# NO2-CO_Schematic.net
KiCad netlist of a schematic drawn in Altium Designer
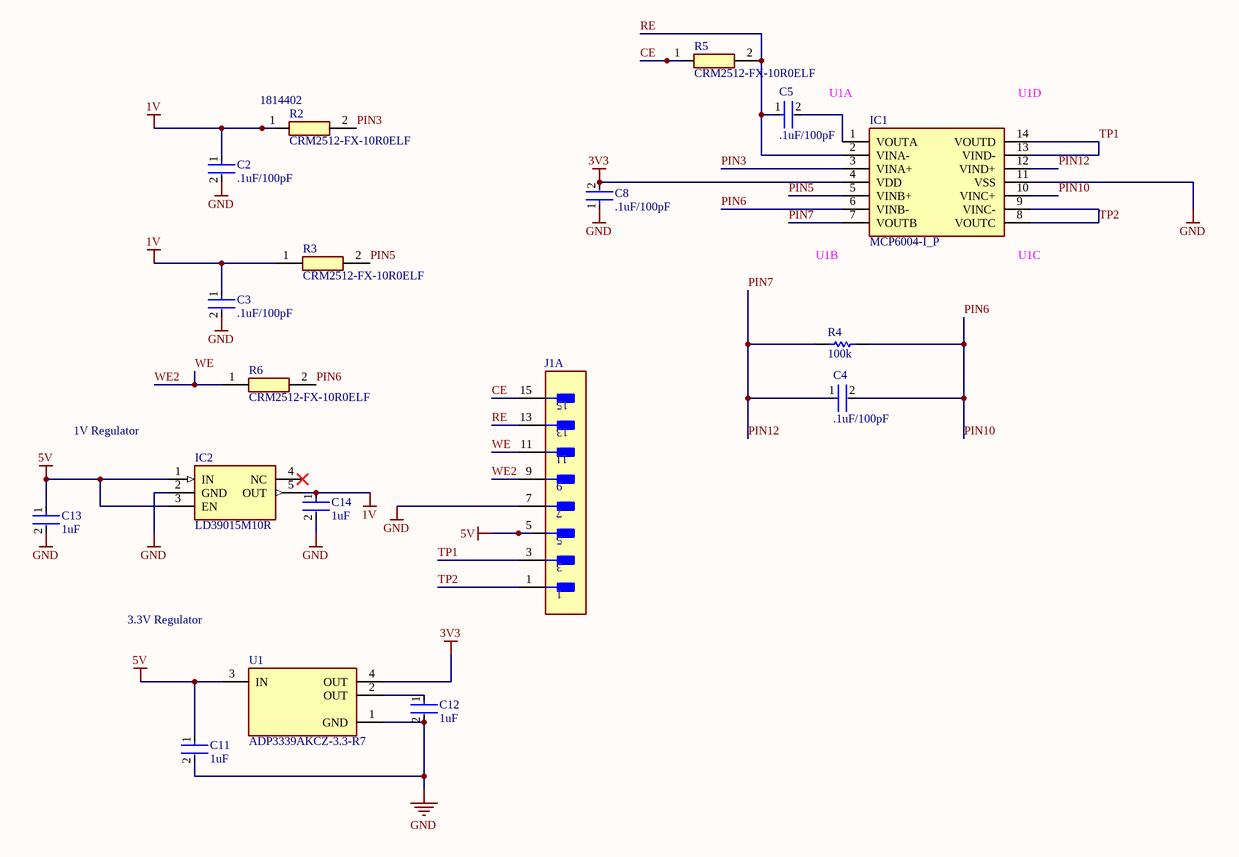
[diagram p0: NO2-CO Schematic.SchDoc]

(export (version "E")
  (design (tool "Eeschema 10.0.6"))
  (components
    (comp (ref "C2")
      (value ".1uF/100pF")
      (footprint "FP-RCE0DB-MFG")
      (description "Cap Ceramic 100pF 100V C0G ±5% Radial 2.5mm +125°C Ammo Pack")
      (fields (field (name "TOLERANCE") "5%"))
      (libsource (lib "Altium Content Vault") (part "b4654b650e69147ec39a6b967a45e02"))
    )
    (comp (ref "C3")
      (value ".1uF/100pF")
      (footprint "FP-RCE0DB-MFG")
      (description "Cap Ceramic 100pF 100V C0G ±5% Radial 2.5mm +125°C Ammo Pack")
      (fields (field (name "TOLERANCE") "5%"))
      (libsource (lib "Altium Content Vault") (part "b4654b650e69147ec39a6b967a45e02"))
    )
    (comp (ref "C4")
      (value ".1uF/100pF")
      (footprint "FP-RCE0DB-MFG")
      (description "Cap Ceramic 100pF 100V C0G ±5% Radial 2.5mm +125°C Ammo Pack")
      (fields (field (name "TOLERANCE") "5%"))
      (libsource (lib "Altium Content Vault") (part "b4654b650e69147ec39a6b967a45e02"))
    )
    (comp (ref "C5")
      (value ".1uF/100pF")
      (footprint "FP-RCE0DB-MFG")
      (description "Cap Ceramic 100pF 100V C0G ±5% Radial 2.5mm +125°C Ammo Pack")
      (fields (field (name "TOLERANCE") "5%"))
      (libsource (lib "Altium Content Vault") (part "b4654b650e69147ec39a6b967a45e02"))
    )
    (comp (ref "C8")
      (value ".1uF/100pF")
      (footprint "FP-RCE0DB-MFG")
      (description "Cap Ceramic 100pF 100V C0G ±5% Radial 2.5mm +125°C Ammo Pack")
      (fields (field (name "TOLERANCE") "5%"))
      (libsource (lib "Altium Content Vault") (part "b4654b650e69147ec39a6b967a45e02"))
    )
    (comp (ref "C11")
      (value "1uF")
      (footprint "FP-0603-L_1_6_0_1-W_0_8_0-IPC_B")
      (description "None")
      (fields (field (name "TOLERANCE") "10%"))
      (libsource (lib "Altium Content Vault") (part "02cd4be3c70576c341d710602a673aa"))
    )
    (comp (ref "C12")
      (value "1uF")
      (footprint "FP-0603-L_1_6_0_1-W_0_8_0-IPC_B")
      (description "None")
      (fields (field (name "TOLERANCE") "10%"))
      (libsource (lib "Altium Content Vault") (part "02cd4be3c70576c341d710602a673aa"))
    )
    (comp (ref "C13")
      (value "1uF")
      (footprint "FP-0603-L_1_6_0_1-W_0_8_0-IPC_B")
      (description "None")
      (fields (field (name "TOLERANCE") "10%"))
      (libsource (lib "Altium Content Vault") (part "02cd4be3c70576c341d710602a673aa"))
    )
    (comp (ref "C14")
      (value "1uF")
      (footprint "FP-0603-L_1_6_0_1-W_0_8_0-IPC_B")
      (description "None")
      (fields (field (name "TOLERANCE") "10%"))
      (libsource (lib "Altium Content Vault") (part "02cd4be3c70576c341d710602a673aa"))
    )
    (comp (ref "IC1")
      (value "MCP6004-I_P")
      (footprint "SamacSys:DIP794W56P254L1905H432Q14N")
      (description "Integrated Circuit")
      (fields
        (field (name "MANUFACTURER_PART_NUMBER") "MCP6004-I/P")
        (field (name "MOUSER PART NUMBER") "579-MCP6004-I/P")
      )
      (libsource (lib "*") (part "MCP6004-I_P"))
    )
    (comp (ref "IC2")
      (value "LD39015M10R")
      (footprint "SamacSys:SOT95P280X145-5N")
      (description "Integrated Circuit")
      (fields (field (name "MOUSER PART NUMBER") "511-LD39015M10R"))
      (libsource (lib "*") (part "LD39015M10R"))
    )
    (comp (ref "J1")
      (value "~")
      (footprint "FP-87227-8-MFG")
      (description "CONN HEADER VERT 16POS 2.54MM")
      (fields
        (field (name "MANUFACTURER") "TE Connectivity")
        (field (name "MANUFACTURER PART NUMBER") "87227-8")
      )
      (libsource (lib "Altium Content Vault") (part "4b6d22b45e2f925f038cba5d936fbcc"))
    )
    (comp (ref "R2")
      (value "CRM2512-FX-10R0ELF")
      (footprint "SamacSys:RESC6331X80N")
      (description "Resistor")
      (fields
        (field (name "MOUSER PART NUMBER") "652-CRM2512FX10R0ELF")
        (field (name "SUPPLIER PART NUMBER 1") "1814402")
      )
      (libsource (lib "*") (part "CRM2512-FX-10R0ELF"))
    )
    (comp (ref "R3")
      (value "CRM2512-FX-10R0ELF")
      (footprint "SamacSys:RESC6331X80N")
      (description "Resistor")
      (fields (field (name "MOUSER PART NUMBER") "652-CRM2512FX10R0ELF"))
      (libsource (lib "*") (part "CRM2512-FX-10R0ELF"))
    )
    (comp (ref "R4")
      (value "100k")
      (footprint "RESA60-630X240")
      (description "Axial Resistor, 100 KOhm, +/- 1%, 0.25 W, -55 to 155 degC, 2-Pin THD, RoHS, Bulk")
      (fields (field (name "TOLERANCE") "1%"))
      (libsource (lib "Altium Content Vault") (part "RES-2"))
    )
    (comp (ref "R5")
      (value "CRM2512-FX-10R0ELF")
      (footprint "SamacSys:RESC6331X80N")
      (description "Resistor")
      (fields (field (name "MOUSER PART NUMBER") "652-CRM2512FX10R0ELF"))
      (libsource (lib "*") (part "CRM2512-FX-10R0ELF"))
    )
    (comp (ref "R6")
      (value "CRM2512-FX-10R0ELF")
      (footprint "SamacSys:RESC6331X80N")
      (description "Resistor")
      (fields (field (name "MOUSER PART NUMBER") "652-CRM2512FX10R0ELF"))
      (libsource (lib "*") (part "CRM2512-FX-10R0ELF"))
    )
    (comp (ref "U1")
      (value "ADP3339AKCZ-3.3-R7")
      (footprint "FP-KC-3-IPC_C")
      (description "IC REG LINEAR 3.3V 1.5A SOT223-3")
      (libsource (lib "Altium Content Vault") (part "9a28c78e4705cf0ec0890e31d7bbefd"))
    )
  )
  (nets
    (net (code "1") (name "/CE") (class "Default")
      (node (ref "J1") (pin "15") (pinfunction "15_15") (pintype "passive"))
      (node (ref "R5") (pin "1") (pinfunction "1_1") (pintype "passive"))
    )
    (net (code "2") (name "/PIN3") (class "Default")
      (node (ref "IC1") (pin "3") (pinfunction "VINA+_3") (pintype "passive"))
      (node (ref "R2") (pin "2") (pinfunction "2_2") (pintype "passive"))
    )
    (net (code "3") (name "/PIN5") (class "Default")
      (node (ref "IC1") (pin "5") (pinfunction "VINB+_5") (pintype "passive"))
      (node (ref "R3") (pin "2") (pinfunction "2_2") (pintype "passive"))
    )
    (net (code "4") (name "/PIN10") (class "Default")
      (node (ref "C4") (pin "2") (pinfunction "2_2") (pintype "passive"))
      (node (ref "IC1") (pin "10") (pinfunction "VINC+_10") (pintype "passive"))
      (node (ref "IC1") (pin "6") (pinfunction "VINB-_6") (pintype "passive"))
      (node (ref "R4") (pin "2") (pinfunction "2_2") (pintype "passive"))
      (node (ref "R6") (pin "2") (pinfunction "2_2") (pintype "passive"))
    )
    (net (code "5") (name "/PIN12") (class "Default")
      (node (ref "C4") (pin "1") (pinfunction "1_1") (pintype "passive"))
      (node (ref "IC1") (pin "12") (pinfunction "VIND+_12") (pintype "passive"))
      (node (ref "IC1") (pin "7") (pinfunction "VOUTB_7") (pintype "passive"))
      (node (ref "R4") (pin "1") (pinfunction "1_1") (pintype "passive"))
    )
    (net (code "6") (name "/RE") (class "Default")
      (node (ref "C5") (pin "1") (pinfunction "1_1") (pintype "passive"))
      (node (ref "IC1") (pin "2") (pinfunction "VINA-_2") (pintype "passive"))
      (node (ref "J1") (pin "13") (pinfunction "13_13") (pintype "passive"))
      (node (ref "R5") (pin "2") (pinfunction "2_2") (pintype "passive"))
    )
    (net (code "7") (name "/TP1") (class "Default")
      (node (ref "IC1") (pin "13") (pinfunction "VIND-_13") (pintype "passive"))
      (node (ref "IC1") (pin "14") (pinfunction "VOUTD_14") (pintype "passive"))
      (node (ref "J1") (pin "3") (pinfunction "3_3") (pintype "passive"))
    )
    (net (code "8") (name "/TP2") (class "Default")
      (node (ref "IC1") (pin "8") (pinfunction "VOUTC_8") (pintype "passive"))
      (node (ref "IC1") (pin "9") (pinfunction "VINC-_9") (pintype "passive"))
      (node (ref "J1") (pin "1") (pinfunction "1_1") (pintype "passive"))
    )
    (net (code "9") (name "/WE") (class "Default")
      (node (ref "J1") (pin "11") (pinfunction "11_11") (pintype "passive"))
      (node (ref "J1") (pin "9") (pinfunction "9_9") (pintype "passive"))
      (node (ref "R6") (pin "1") (pinfunction "1_1") (pintype "passive"))
    )
    (net (code "10") (name "1V") (class "Default")
      (node (ref "C14") (pin "1") (pinfunction "1_1") (pintype "passive"))
      (node (ref "C2") (pin "1") (pinfunction "1_1") (pintype "passive"))
      (node (ref "C3") (pin "1") (pinfunction "1_1") (pintype "passive"))
      (node (ref "IC2") (pin "5") (pinfunction "OUT_5") (pintype "output"))
      (node (ref "R2") (pin "1") (pinfunction "1_1") (pintype "passive"))
      (node (ref "R3") (pin "1") (pinfunction "1_1") (pintype "passive"))
    )
    (net (code "11") (name "3V3") (class "Default")
      (node (ref "C8") (pin "2") (pinfunction "2_2") (pintype "passive"))
      (node (ref "IC1") (pin "4") (pinfunction "VDD_4") (pintype "passive"))
      (node (ref "U1") (pin "4") (pinfunction "OUT_4") (pintype "power_in"))
    )
    (net (code "12") (name "5V") (class "Default")
      (node (ref "C11") (pin "1") (pinfunction "1_1") (pintype "passive"))
      (node (ref "C13") (pin "1") (pinfunction "1_1") (pintype "passive"))
      (node (ref "IC2") (pin "1") (pinfunction "IN_1") (pintype "input"))
      (node (ref "IC2") (pin "3") (pinfunction "EN_3") (pintype "passive"))
      (node (ref "J1") (pin "5") (pinfunction "5_5") (pintype "passive"))
      (node (ref "U1") (pin "3") (pinfunction "IN_3") (pintype "power_in"))
    )
    (net (code "13") (name "GND") (class "Default")
      (node (ref "C11") (pin "2") (pinfunction "2_2") (pintype "passive"))
      (node (ref "C12") (pin "2") (pinfunction "2_2") (pintype "passive"))
      (node (ref "C13") (pin "2") (pinfunction "2_2") (pintype "passive"))
      (node (ref "C14") (pin "2") (pinfunction "2_2") (pintype "passive"))
      (node (ref "C2") (pin "2") (pinfunction "2_2") (pintype "passive"))
      (node (ref "C3") (pin "2") (pinfunction "2_2") (pintype "passive"))
      (node (ref "C8") (pin "1") (pinfunction "1_1") (pintype "passive"))
      (node (ref "IC1") (pin "11") (pinfunction "VSS_11") (pintype "passive"))
      (node (ref "IC2") (pin "2") (pinfunction "GND_2") (pintype "power_in"))
      (node (ref "J1") (pin "7") (pinfunction "7_7") (pintype "passive"))
      (node (ref "U1") (pin "1") (pinfunction "GND_1") (pintype "power_in"))
    )
    (net (code "14") (name "Net-(C12-Pad1)") (class "Default")
      (node (ref "C12") (pin "1") (pinfunction "1_1") (pintype "passive"))
      (node (ref "U1") (pin "2") (pinfunction "OUT_2") (pintype "power_in"))
    )
    (net (code "15") (name "Net-(IC1-VOUTA)") (class "Default")
      (node (ref "C5") (pin "2") (pinfunction "2_2") (pintype "passive"))
      (node (ref "IC1") (pin "1") (pinfunction "VOUTA_1") (pintype "passive"))
    )
    (net (code "16") (name "unconnected-(IC2-NC-Pad4)") (class "Default")
      (node (ref "IC2") (pin "4") (pinfunction "NC_4") (pintype "passive+no_connect"))
    )
  )
)
